# Bee_Hive_Scale_Board_3_1.net
KiCad netlist of a schematic drawn in Altium Designer
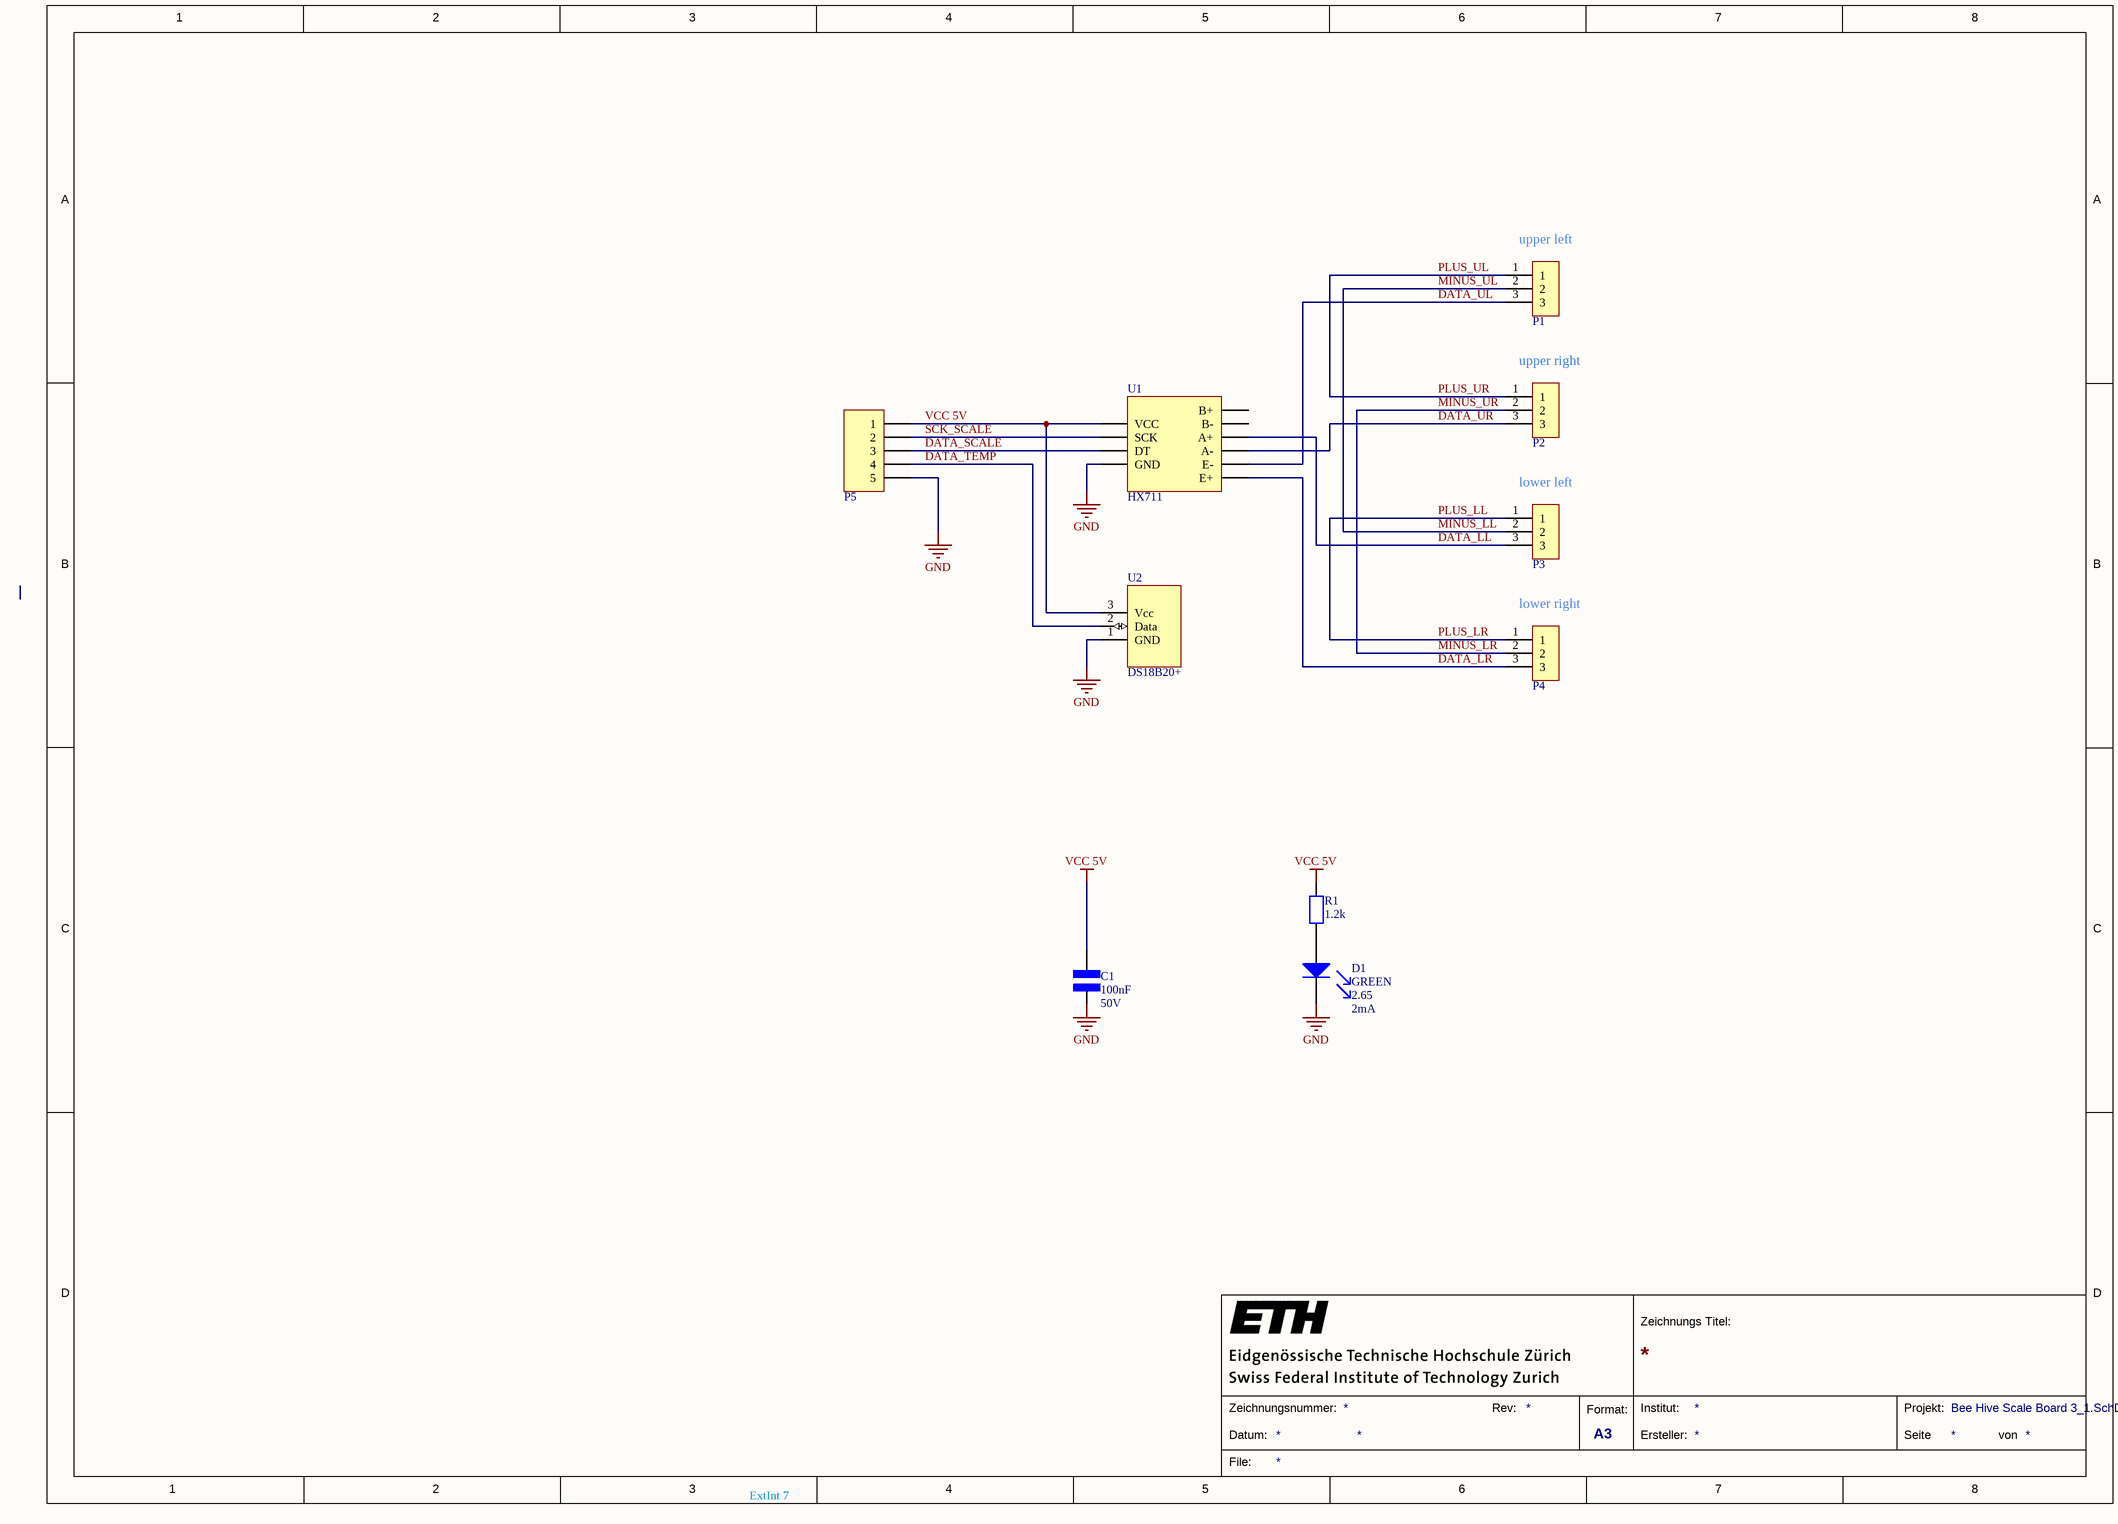
[diagram p0: Bee Hive Scale Board 3_1.SchDoc]

(export (version "E")
  (design (tool "Eeschema 10.0.6"))
  (components
    (comp (ref "C1")
      (value "100nF")
      (footprint "CAP 0603")
      (description "C CERAMIC SMD")
      (fields (field (name "UMAX") "50V") (field (name "Comment") "100nF 0603_1"))
      (libsource (lib "Library CAP") (part "100nF 0603_1"))
    )
    (comp (ref "D1")
      (value "LED Diode SMD LOW CURRENT")
      (footprint "LED SMD 0603 FOOTPRINT")
      (description "APT1608LZGCK")
      (fields
        (field (name "COLOR") "GREEN")
        (field (name "FORWARD VOLTAGE") "2.65")
        (field (name "IF") "2mA")
      )
      (libsource (lib "Library DIODE") (part "LED Diode SMD - GREEN - 0603 - 2mA_1"))
    )
    (comp (ref "P1")
      (value "3-Pin Right Angle Housing")
      (footprint "3PIN - Connector right angle")
      (description "3-Pin")
      (libsource (lib "Library Scematic") (part "3-Pin Right Angle"))
    )
    (comp (ref "P2")
      (value "3-Pin Right Angle Housing")
      (footprint "3PIN - Connector right angle")
      (description "3-Pin")
      (libsource (lib "Library Scematic") (part "3-Pin Right Angle"))
    )
    (comp (ref "P3")
      (value "3-Pin Right Angle Housing")
      (footprint "3PIN - Connector right angle")
      (description "3-Pin")
      (libsource (lib "Library Scematic") (part "3-Pin Right Angle"))
    )
    (comp (ref "P4")
      (value "3-Pin Right Angle Housing")
      (footprint "3PIN - Connector right angle")
      (description "3-Pin")
      (libsource (lib "Library Scematic") (part "3-Pin Right Angle"))
    )
    (comp (ref "P5")
      (value "comment")
      (footprint "5PIN")
      (description "5-Pin")
      (libsource (lib "Library Scematic") (part "5-Pin"))
    )
    (comp (ref "R1")
      (value "1.2k")
      (footprint "RES 0603 FOOTPRINT")
      (description "R SMD")
      (fields (field (name "Comment") "1.2k Ohm 0603"))
      (libsource (lib "Library RES") (part "1.2k Ohm 0603"))
    )
    (comp (ref "U1")
      (value "HX711")
      (footprint "HX711 SCALE - long")
      (description "HX711 XFW Alibaba Board")
      (libsource (lib "Library Scematic") (part "HX711 XFW Alibaba Board"))
    )
    (comp (ref "U2")
      (value "DS18B20+")
      (footprint "DS1820 Footprint")
      (description "Temperature Sensor, 12 Bit, OneWire, 3-pin TO-92")
      (libsource (lib "Library Scematic") (part "DS18B20"))
    )
  )
  (nets
    (net (code "1") (name "/DATA_LL") (class "Default")
      (node (ref "P3") (pin "3") (pinfunction "3_3") (pintype "passive"))
      (node (ref "U1") (pin "4") (pinfunction "A+_4") (pintype "passive"))
    )
    (net (code "2") (name "/DATA_LR") (class "Default")
      (node (ref "P4") (pin "3") (pinfunction "3_3") (pintype "passive"))
      (node (ref "U1") (pin "1") (pinfunction "E+_1") (pintype "passive"))
    )
    (net (code "3") (name "/DATA_SCALE") (class "Default")
      (node (ref "P5") (pin "3") (pinfunction "3_3") (pintype "passive"))
      (node (ref "U1") (pin "8") (pinfunction "DT_8") (pintype "passive"))
    )
    (net (code "4") (name "/DATA_TEMP") (class "Default")
      (node (ref "P5") (pin "4") (pinfunction "4_4") (pintype "passive"))
      (node (ref "U2") (pin "2") (pinfunction "Data_2") (pintype "bidirectional"))
    )
    (net (code "5") (name "/DATA_UL") (class "Default")
      (node (ref "P1") (pin "3") (pinfunction "3_3") (pintype "passive"))
      (node (ref "U1") (pin "2") (pinfunction "E-_2") (pintype "passive"))
    )
    (net (code "6") (name "/DATA_UR") (class "Default")
      (node (ref "P2") (pin "3") (pinfunction "3_3") (pintype "passive"))
      (node (ref "U1") (pin "3") (pinfunction "A-_3") (pintype "passive"))
    )
    (net (code "7") (name "/MINUS_LL") (class "Default")
      (node (ref "P1") (pin "2") (pinfunction "2_2") (pintype "passive"))
      (node (ref "P3") (pin "2") (pinfunction "2_2") (pintype "passive"))
    )
    (net (code "8") (name "/MINUS_LR") (class "Default")
      (node (ref "P2") (pin "2") (pinfunction "2_2") (pintype "passive"))
      (node (ref "P4") (pin "2") (pinfunction "2_2") (pintype "passive"))
    )
    (net (code "9") (name "/PLUS_LL") (class "Default")
      (node (ref "P3") (pin "1") (pinfunction "1_1") (pintype "passive"))
      (node (ref "P4") (pin "1") (pinfunction "1_1") (pintype "passive"))
    )
    (net (code "10") (name "/PLUS_UL") (class "Default")
      (node (ref "P1") (pin "1") (pinfunction "1_1") (pintype "passive"))
      (node (ref "P2") (pin "1") (pinfunction "1_1") (pintype "passive"))
    )
    (net (code "11") (name "/SCK_SCALE") (class "Default")
      (node (ref "P5") (pin "2") (pinfunction "2_2") (pintype "passive"))
      (node (ref "U1") (pin "9") (pinfunction "SCK_9") (pintype "passive"))
    )
    (net (code "12") (name "GND") (class "Default")
      (node (ref "C1") (pin "1") (pinfunction "1_1") (pintype "passive"))
      (node (ref "D1") (pin "2") (pinfunction "K_2") (pintype "passive"))
      (node (ref "P5") (pin "5") (pinfunction "5_5") (pintype "passive"))
      (node (ref "U1") (pin "7") (pinfunction "GND_7") (pintype "passive"))
      (node (ref "U2") (pin "1") (pinfunction "GND_1") (pintype "power_in"))
    )
    (net (code "13") (name "Net-(D1-A)") (class "Default")
      (node (ref "D1") (pin "1") (pinfunction "A_1") (pintype "passive"))
      (node (ref "R1") (pin "1") (pinfunction "1_1") (pintype "passive"))
    )
    (net (code "14") (name "VCC 5V") (class "Default")
      (node (ref "C1") (pin "2") (pinfunction "2_2") (pintype "passive"))
      (node (ref "P5") (pin "1") (pinfunction "1_1") (pintype "passive"))
      (node (ref "R1") (pin "2") (pinfunction "2_2") (pintype "passive"))
      (node (ref "U1") (pin "10") (pinfunction "VCC_10") (pintype "passive"))
      (node (ref "U2") (pin "3") (pinfunction "Vcc_3") (pintype "power_in"))
    )
    (net (code "15") (name "unconnected-(U1-B+-Pad6)") (class "Default")
      (node (ref "U1") (pin "6") (pinfunction "B+_6") (pintype "passive"))
    )
    (net (code "16") (name "unconnected-(U1-B--Pad5)") (class "Default")
      (node (ref "U1") (pin "5") (pinfunction "B-_5") (pintype "passive"))
    )
  )
)
